# EasyEDA_ProPrj_Magnetic_Pole_Detector.net
KiCad netlist of a schematic drawn in EasyEDA Pro
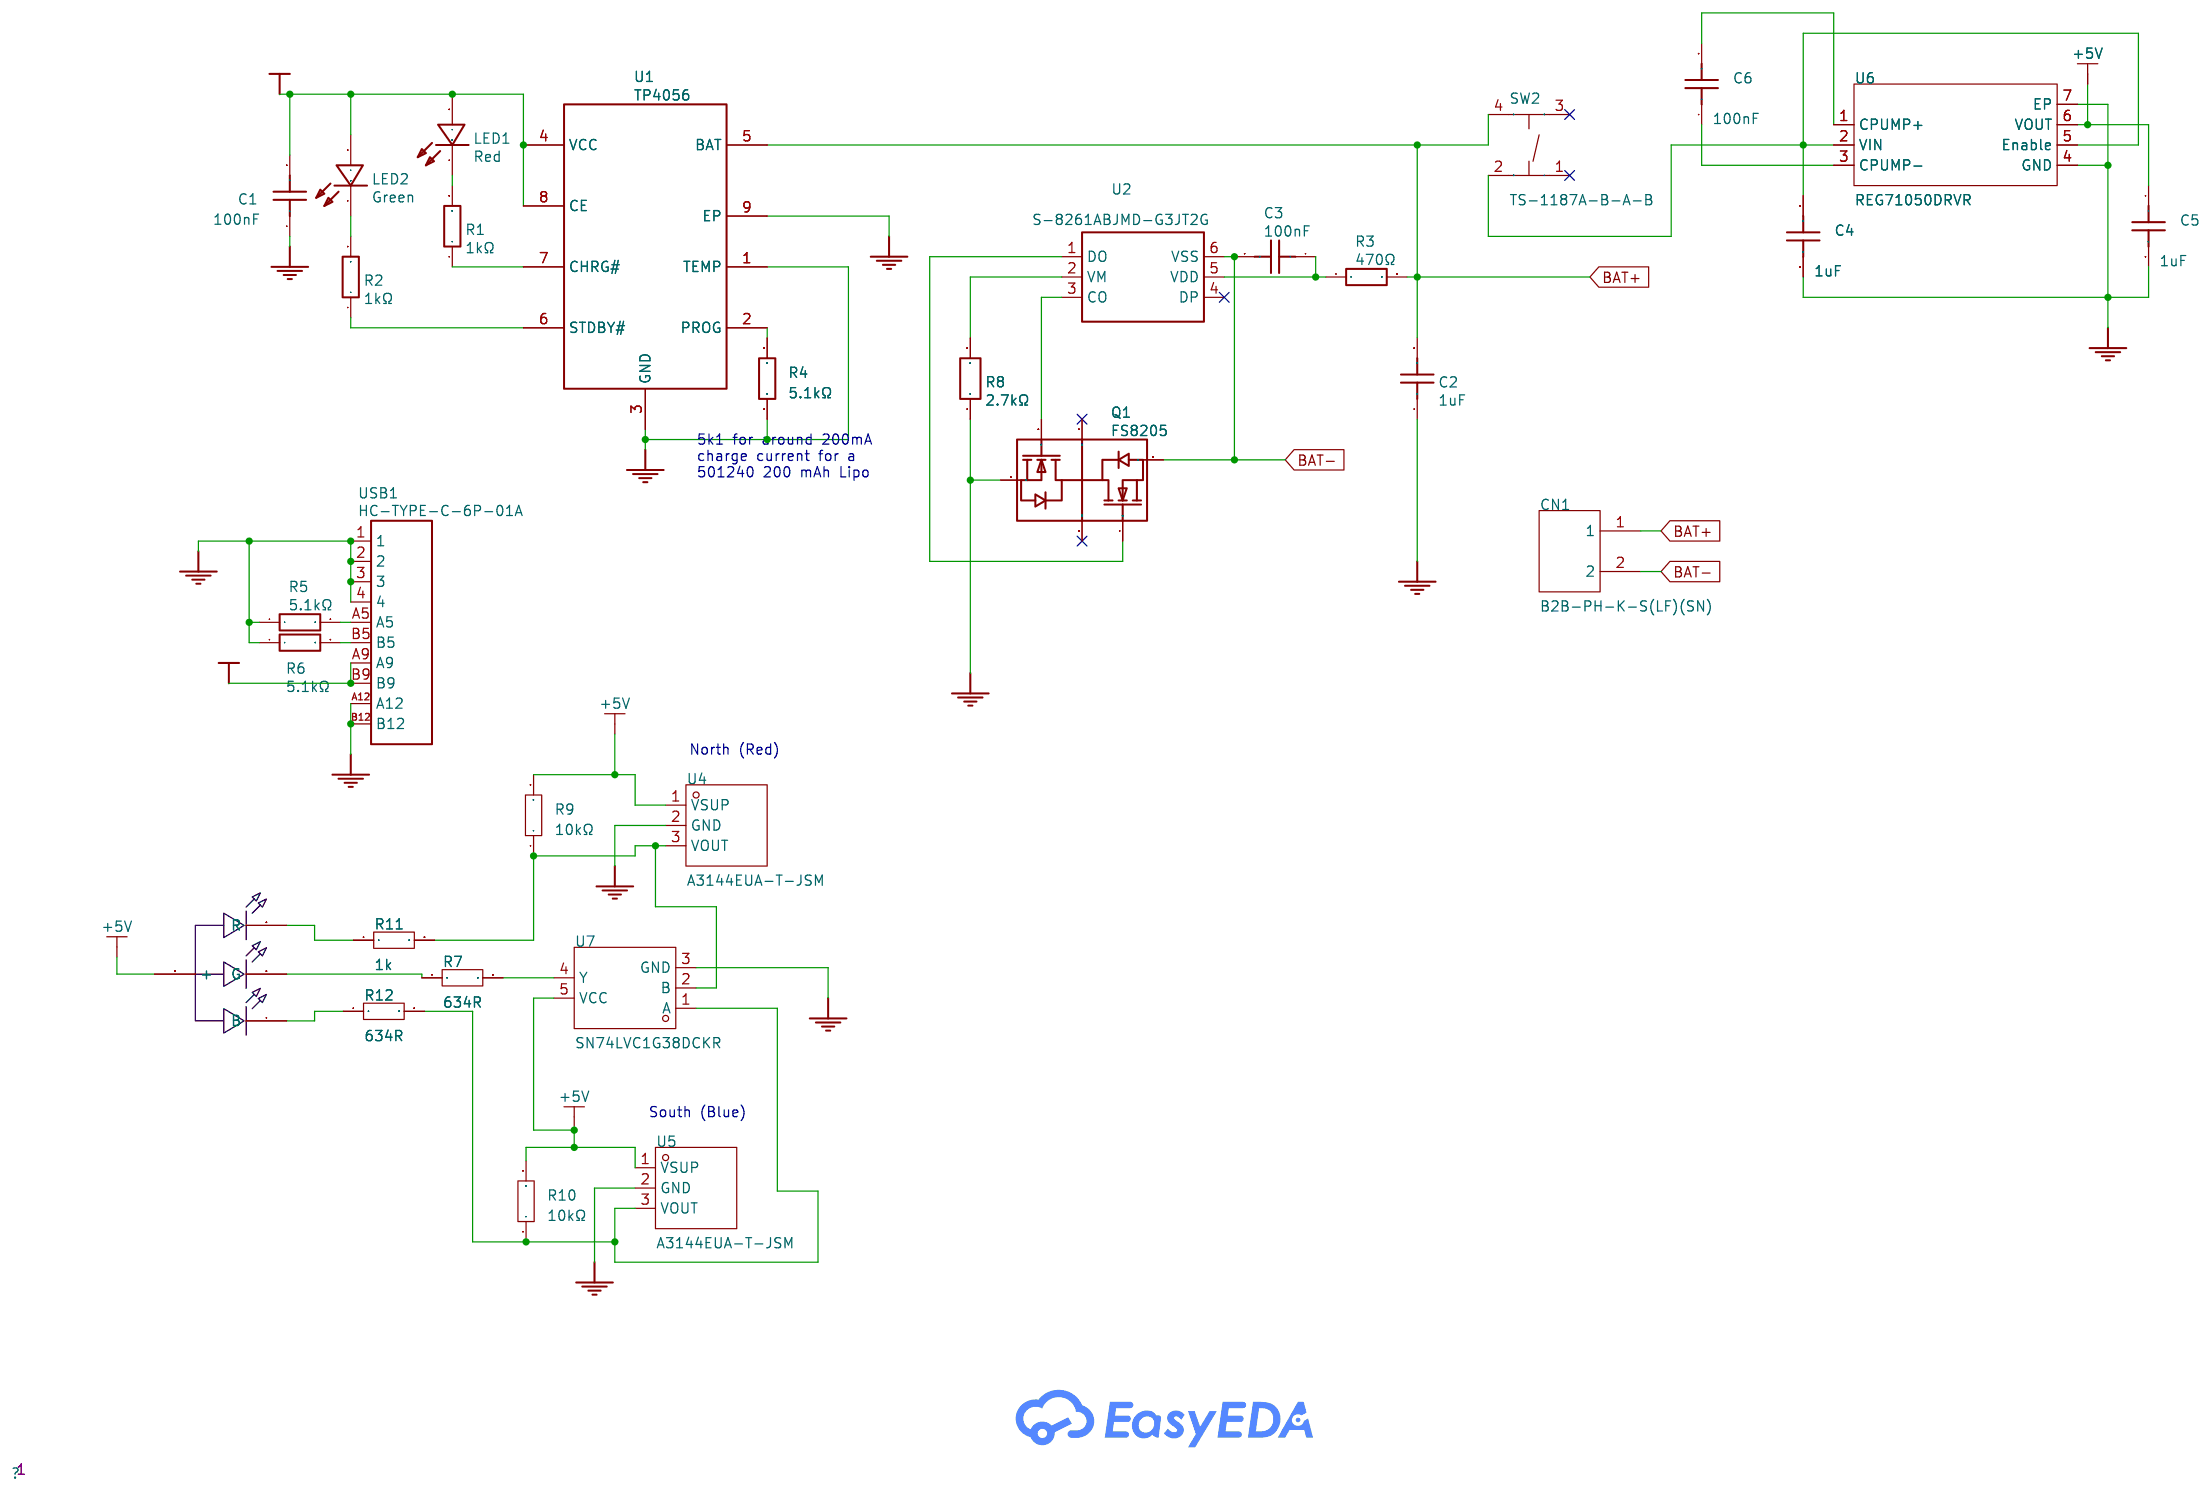
[diagram p0: schematic sheet]

(export (version "E")
  (design (tool "Eeschema 10.0.6"))
  (components
    (comp (ref "C1")
      (value "100nF")
      (footprint "easyedapro:C0402")
      (fields (field (name "Manufacturer Part") "CC0402KRX7R7BB104") (field (name "Manufacturer") "YAGEO"))
      (libsource (lib "easyedapro") (part "100nF"))
    )
    (comp (ref "C2")
      (value "1uF")
      (footprint "easyedapro:C0402")
      (fields (field (name "Manufacturer Part") "0402X106M100NT") (field (name "Manufacturer") "FH(风华)"))
      (libsource (lib "easyedapro") (part "10uF"))
    )
    (comp (ref "C3")
      (value "100nF")
      (footprint "easyedapro:C0402")
      (fields (field (name "Manufacturer Part") "CC0402KRX7R7BB104") (field (name "Manufacturer") "YAGEO"))
      (libsource (lib "easyedapro") (part "100nF"))
    )
    (comp (ref "C4")
      (value "1uF")
      (footprint "easyedapro:C0402")
      (fields (field (name "Manufacturer Part") "CC0402KRX7R7BB104") (field (name "Manufacturer") "YAGEO"))
      (libsource (lib "easyedapro") (part "100nF"))
    )
    (comp (ref "C5")
      (value "1uF")
      (footprint "easyedapro:C0402")
      (fields (field (name "Manufacturer Part") "CC0402KRX7R7BB104") (field (name "Manufacturer") "YAGEO"))
      (libsource (lib "easyedapro") (part "100nF"))
    )
    (comp (ref "C6")
      (value "100nF")
      (footprint "easyedapro:C0402")
      (fields (field (name "Manufacturer Part") "CC0402KRX7R7BB104") (field (name "Manufacturer") "YAGEO"))
      (libsource (lib "easyedapro") (part "100nF"))
    )
    (comp (ref "CN1")
      (value "B2B-PH-K-S(LF)(SN)")
      (footprint "easyedapro:CONN-TH_B2B-PH-K-S")
      (fields (field (name "Manufacturer") "JST"))
      (libsource (lib "easyedapro") (part "B2B-PH-K-S(LF)(SN)"))
    )
    (comp (ref "LED1")
      (value "Red")
      (footprint "easyedapro:LED0603-RD_RED")
      (fields
        (field (name "Manufacturer Part") "TJ-S1608SW6THBLC2R-A5")
        (field (name "Manufacturer") "TOGIALED(统佳)")
        (field (name "Contributor") "LCSC")
      )
      (libsource (lib "easyedapro") (part "Red"))
    )
    (comp (ref "LED2")
      (value "Green")
      (footprint "easyedapro:LED0603-RD_RED")
      (fields
        (field (name "Manufacturer Part") "TJ-S1608SW6TGLC7K-A5")
        (field (name "Manufacturer") "TOGIALED(统佳)")
        (field (name "Contributor") "LCSC")
      )
      (libsource (lib "easyedapro") (part "Green"))
    )
    (comp (ref "LED3")
      (value "LED 5mm RGB")
      (footprint "easyedapro:5MM RGB TRI-COLOR LED 1.25MM PINS")
      (description "Common Anode RGB LED for general purpose lighting")
      (libsource (lib "easyedapro") (part "RGB_LED_Common_Anode"))
    )
    (comp (ref "Q1")
      (value "FS8205")
      (footprint "easyedapro:SOT-23-6_L2.9-W1.6-P0.95-LS2.8-BR")
      (fields (field (name "Manufacturer Part") "FS8205A") (field (name "Manufacturer") "FUXINSEMI(富芯森美)"))
      (libsource (lib "easyedapro") (part "FS8205"))
    )
    (comp (ref "R1")
      (value "1kΩ")
      (footprint "easyedapro:R0402")
      (fields
        (field (name "Manufacturer Part") "0402WGF1001TCE")
        (field (name "Manufacturer") "UNI-ROYAL(厚声)")
      )
      (libsource (lib "easyedapro") (part "1kΩ"))
    )
    (comp (ref "R2")
      (value "1kΩ")
      (footprint "easyedapro:R0402")
      (fields
        (field (name "Manufacturer Part") "0402WGF1001TCE")
        (field (name "Manufacturer") "UNI-ROYAL(厚声)")
      )
      (libsource (lib "easyedapro") (part "1kΩ"))
    )
    (comp (ref "R3")
      (value "470Ω")
      (footprint "easyedapro:R0402")
      (fields
        (field (name "Manufacturer Part") "0402WGF4700TCE")
        (field (name "Manufacturer") "UNI-ROYAL(厚声)")
      )
      (libsource (lib "easyedapro") (part "470Ω"))
    )
    (comp (ref "R4")
      (value "5.1kΩ")
      (footprint "easyedapro:R0402")
      (fields
        (field (name "Manufacturer Part") "0402WGF5101TCE")
        (field (name "Manufacturer") "UNI-ROYAL(厚声)")
      )
      (libsource (lib "easyedapro") (part "5.1kΩ"))
    )
    (comp (ref "R5")
      (value "5.1kΩ")
      (footprint "easyedapro:R0402")
      (fields
        (field (name "Manufacturer Part") "0402WGF5101TCE")
        (field (name "Manufacturer") "UNI-ROYAL(厚声)")
      )
      (libsource (lib "easyedapro") (part "5.1kΩ"))
    )
    (comp (ref "R6")
      (value "5.1kΩ")
      (footprint "easyedapro:R0402")
      (fields
        (field (name "Manufacturer Part") "0402WGF5101TCE")
        (field (name "Manufacturer") "UNI-ROYAL(厚声)")
      )
      (libsource (lib "easyedapro") (part "5.1kΩ"))
    )
    (comp (ref "R7")
      (value "634R")
      (footprint "easyedapro:R0603")
      (libsource (lib "easyedapro") (part "Res"))
    )
    (comp (ref "R8")
      (value "2.7kΩ")
      (footprint "easyedapro:R0402")
      (fields
        (field (name "Manufacturer Part") "0402WGF2701TCE")
        (field (name "Manufacturer") "UNI-ROYAL(厚声)")
        (field (name "Contributor") "LCSC")
      )
      (libsource (lib "easyedapro") (part "2.7kΩ"))
    )
    (comp (ref "R9")
      (value "10kΩ")
      (footprint "easyedapro:R0603")
      (fields (field (name "Manufacturer Part") "FCR0402F10K") (field (name "Manufacturer") "VO(翔胜)"))
      (libsource (lib "easyedapro") (part "Res"))
    )
    (comp (ref "R10")
      (value "10kΩ")
      (footprint "easyedapro:R0603")
      (fields (field (name "Manufacturer Part") "SCR0402F10K") (field (name "Manufacturer") "VO(翔胜)"))
      (libsource (lib "easyedapro") (part "Res"))
    )
    (comp (ref "R11") (value "1k") (footprint "easyedapro:R0603") (libsource (lib "easyedapro") (part "Res")))
    (comp (ref "R12")
      (value "634R")
      (footprint "easyedapro:R0603")
      (libsource (lib "easyedapro") (part "Res"))
    )
    (comp (ref "SW2")
      (value "TS-1187A-B-A-B")
      (footprint "easyedapro:SW-SMD_4P-L5.1-W5.1-P3.70-LS6.5-TL_H1.5")
      (fields (field (name "Manufacturer") "XKB Connection(中国星坤)"))
      (libsource (lib "easyedapro") (part "TS-1187A-B-A-B"))
    )
    (comp (ref "U1")
      (value "TP4056")
      (footprint "easyedapro:ESOP-8_L4.9-W3.9-P1.27-LS6.0-BL-EP")
      (fields (field (name "Manufacturer") "UMW") (field (name "Contributor") "Guest"))
      (libsource (lib "easyedapro") (part "TP4056"))
    )
    (comp (ref "U2")
      (value "S-8261ABJMD-G3JT2G")
      (footprint "easyedapro:SOT-23-6_L2.9-W1.6-P0.95-LS2.8-TL")
      (fields
        (field (name "Manufacturer Part") "S-8261ABJMD-G3JT2S")
        (field (name "Manufacturer") "ABLIC(艾普凌科)")
      )
      (libsource (lib "easyedapro") (part "S-8261ABJMD-G3JT2G"))
    )
    (comp (ref "U4")
      (value "A3144EUA-T-JSM")
      (footprint "easyedapro:TO-92S-3_L4.1-W1.7-P1.27-L")
      (fields (field (name "Manufacturer") "JSMSEMI(杰盛微)"))
      (libsource (lib "easyedapro") (part "A3144EUA-T-JSM"))
    )
    (comp (ref "U5")
      (value "A3144EUA-T-JSM")
      (footprint "easyedapro:TO-92S-3_L4.1-W1.7-P1.27-L")
      (fields (field (name "Manufacturer") "JSMSEMI(杰盛微)"))
      (libsource (lib "easyedapro") (part "A3144EUA-T-JSM"))
    )
    (comp (ref "U6")
      (value "REG71050DRVR")
      (footprint "easyedapro:WSON-6_L2.0-W2.0-P0.65-TL-EP")
      (fields (field (name "Manufacturer") "TI(德州仪器)"))
      (libsource (lib "easyedapro") (part "REG71050DRVR"))
    )
    (comp (ref "U7")
      (value "SN74LVC1G38DCKR")
      (footprint "easyedapro:SC-70-5_L2.1-W1.3-P0.65-LS2.1-BL")
      (fields (field (name "Manufacturer") "TI(德州仪器)"))
      (libsource (lib "easyedapro") (part "SN74LVC1G38DCKR"))
    )
    (comp (ref "USB1")
      (value "HC-TYPE-C-6P-01A")
      (footprint "easyedapro:USB-C-SMD_HC-TYPE-C-6P-01A")
      (fields (field (name "Manufacturer") "HCTL(华灿天禄)") (field (name "Contributor") "LCSC"))
      (libsource (lib "easyedapro") (part "HC-TYPE-C-6P-01A"))
    )
  )
  (nets
    (net (code "1") (name "+5V") (class "Default")
      (node (ref "C5") (pin "1") (pinfunction "1_1") (pintype "unspecified"))
      (node (ref "LED3") (pin "1") (pinfunction "+_1") (pintype "input"))
      (node (ref "R10") (pin "2") (pinfunction "2_2") (pintype "input"))
      (node (ref "R9") (pin "2") (pinfunction "2_2") (pintype "input"))
      (node (ref "U4") (pin "1") (pinfunction "VSUP_1") (pintype "unspecified"))
      (node (ref "U5") (pin "1") (pinfunction "VSUP_1") (pintype "unspecified"))
      (node (ref "U6") (pin "6") (pinfunction "VOUT_6") (pintype "unspecified"))
      (node (ref "U7") (pin "5") (pinfunction "VCC_5") (pintype "unspecified"))
    )
    (net (code "2") (name "BAT+") (class "Default")
      (node (ref "C2") (pin "2") (pinfunction "2_2") (pintype "unspecified"))
      (node (ref "CN1") (pin "1") (pinfunction "1_1") (pintype "input"))
      (node (ref "R3") (pin "2") (pinfunction "2_2") (pintype "input"))
      (node (ref "SW2") (pin "4") (pinfunction "D_4") (pintype "unspecified"))
      (node (ref "U1") (pin "5") (pinfunction "BAT_5") (pintype "unspecified"))
    )
    (net (code "3") (name "BAT-") (class "Default")
      (node (ref "C3") (pin "2") (pinfunction "2_2") (pintype "unspecified"))
      (node (ref "CN1") (pin "2") (pinfunction "2_2") (pintype "input"))
      (node (ref "Q1") (pin "3") (pinfunction "S2_3") (pintype "unspecified"))
      (node (ref "U2") (pin "6") (pinfunction "VSS_6") (pintype "unspecified"))
    )
    (net (code "4") (name "GND") (class "Default")
      (node (ref "C1") (pin "1") (pinfunction "1_1") (pintype "unspecified"))
      (node (ref "C2") (pin "1") (pinfunction "1_1") (pintype "unspecified"))
      (node (ref "C4") (pin "2") (pinfunction "2_2") (pintype "unspecified"))
      (node (ref "C5") (pin "2") (pinfunction "2_2") (pintype "unspecified"))
      (node (ref "Q1") (pin "1") (pinfunction "S1_1") (pintype "unspecified"))
      (node (ref "R4") (pin "1") (pinfunction "1_1") (pintype "input"))
      (node (ref "R5") (pin "1") (pinfunction "1_1") (pintype "input"))
      (node (ref "R6") (pin "1") (pinfunction "1_1") (pintype "input"))
      (node (ref "R8") (pin "1") (pinfunction "1_1") (pintype "unspecified"))
      (node (ref "U1") (pin "1") (pinfunction "TEMP_1") (pintype "unspecified"))
      (node (ref "U1") (pin "3") (pinfunction "GND_3") (pintype "unspecified"))
      (node (ref "U1") (pin "9") (pinfunction "EP_9") (pintype "unspecified"))
      (node (ref "U4") (pin "2") (pinfunction "GND_2") (pintype "unspecified"))
      (node (ref "U5") (pin "2") (pinfunction "GND_2") (pintype "unspecified"))
      (node (ref "U6") (pin "4") (pinfunction "GND_4") (pintype "unspecified"))
      (node (ref "U6") (pin "7") (pinfunction "EP_7") (pintype "unspecified"))
      (node (ref "U7") (pin "3") (pinfunction "GND_3") (pintype "unspecified"))
      (node (ref "USB1") (pin "1") (pinfunction "1_1") (pintype "unspecified"))
      (node (ref "USB1") (pin "2") (pinfunction "2_2") (pintype "unspecified"))
      (node (ref "USB1") (pin "3") (pinfunction "3_3") (pintype "unspecified"))
      (node (ref "USB1") (pin "4") (pinfunction "4_4") (pintype "unspecified"))
      (node (ref "USB1") (pin "A12") (pinfunction "A12_A12") (pintype "unspecified"))
      (node (ref "USB1") (pin "B12") (pinfunction "B12_B12") (pintype "unspecified"))
    )
    (net (code "5") (name "Net-(LED1-C)") (class "Default")
      (node (ref "LED1") (pin "1") (pinfunction "C_1") (pintype "unspecified"))
      (node (ref "R1") (pin "2") (pinfunction "2_2") (pintype "input"))
    )
    (net (code "6") (name "Net-(LED2-C)") (class "Default")
      (node (ref "LED2") (pin "1") (pinfunction "C_1") (pintype "unspecified"))
      (node (ref "R2") (pin "2") (pinfunction "2_2") (pintype "input"))
    )
    (net (code "7") (name "Net-(LED3-B)") (class "Default")
      (node (ref "LED3") (pin "4") (pinfunction "B_4") (pintype "input"))
      (node (ref "R12") (pin "1") (pinfunction "1_1") (pintype "input"))
    )
    (net (code "8") (name "Net-(LED3-G)") (class "Default")
      (node (ref "LED3") (pin "3") (pinfunction "G_3") (pintype "input"))
      (node (ref "R7") (pin "1") (pinfunction "1_1") (pintype "input"))
    )
    (net (code "9") (name "Net-(LED3-R)") (class "Default")
      (node (ref "LED3") (pin "2") (pinfunction "R_2") (pintype "input"))
      (node (ref "R11") (pin "1") (pinfunction "1_1") (pintype "input"))
    )
    (net (code "10") (name "Net-(Q1-G1)") (class "Default")
      (node (ref "Q1") (pin "6") (pinfunction "G1_6") (pintype "unspecified"))
      (node (ref "U2") (pin "3") (pinfunction "CO_3") (pintype "unspecified"))
    )
    (net (code "11") (name "Net-(Q1-G2)") (class "Default")
      (node (ref "Q1") (pin "4") (pinfunction "G2_4") (pintype "unspecified"))
      (node (ref "U2") (pin "1") (pinfunction "DO_1") (pintype "unspecified"))
    )
    (net (code "12") (name "Net-(R5-Pad2)") (class "Default")
      (node (ref "R5") (pin "2") (pinfunction "2_2") (pintype "input"))
      (node (ref "USB1") (pin "A5") (pinfunction "A5_A5") (pintype "unspecified"))
    )
    (net (code "13") (name "Net-(R6-Pad2)") (class "Default")
      (node (ref "R6") (pin "2") (pinfunction "2_2") (pintype "input"))
      (node (ref "USB1") (pin "B5") (pinfunction "B5_B5") (pintype "unspecified"))
    )
    (net (code "14") (name "Net-(SW2-B)") (class "Default")
      (node (ref "C4") (pin "1") (pinfunction "1_1") (pintype "unspecified"))
      (node (ref "SW2") (pin "2") (pinfunction "B_2") (pintype "unspecified"))
      (node (ref "U6") (pin "2") (pinfunction "VIN_2") (pintype "unspecified"))
      (node (ref "U6") (pin "5") (pinfunction "Enable_5") (pintype "unspecified"))
    )
    (net (code "15") (name "Net-(U1-CHRG#)") (class "Default")
      (node (ref "R1") (pin "1") (pinfunction "1_1") (pintype "input"))
      (node (ref "U1") (pin "7") (pinfunction "CHRG#_7") (pintype "unspecified"))
    )
    (net (code "16") (name "Net-(U1-PROG)") (class "Default")
      (node (ref "R4") (pin "2") (pinfunction "2_2") (pintype "input"))
      (node (ref "U1") (pin "2") (pinfunction "PROG_2") (pintype "unspecified"))
    )
    (net (code "17") (name "Net-(U1-STDBY#)") (class "Default")
      (node (ref "R2") (pin "1") (pinfunction "1_1") (pintype "input"))
      (node (ref "U1") (pin "6") (pinfunction "STDBY#_6") (pintype "unspecified"))
    )
    (net (code "18") (name "Net-(U2-VDD)") (class "Default")
      (node (ref "C3") (pin "1") (pinfunction "1_1") (pintype "unspecified"))
      (node (ref "R3") (pin "1") (pinfunction "1_1") (pintype "input"))
      (node (ref "U2") (pin "5") (pinfunction "VDD_5") (pintype "unspecified"))
    )
    (net (code "19") (name "Net-(U2-VM)") (class "Default")
      (node (ref "R8") (pin "2") (pinfunction "2_2") (pintype "unspecified"))
      (node (ref "U2") (pin "2") (pinfunction "VM_2") (pintype "unspecified"))
    )
    (net (code "20") (name "Net-(U4-VOUT)") (class "Default")
      (node (ref "R11") (pin "2") (pinfunction "2_2") (pintype "input"))
      (node (ref "R9") (pin "1") (pinfunction "1_1") (pintype "input"))
      (node (ref "U4") (pin "3") (pinfunction "VOUT_3") (pintype "unspecified"))
      (node (ref "U7") (pin "2") (pinfunction "B_2") (pintype "unspecified"))
    )
    (net (code "21") (name "Net-(U5-VOUT)") (class "Default")
      (node (ref "R10") (pin "1") (pinfunction "1_1") (pintype "input"))
      (node (ref "R12") (pin "2") (pinfunction "2_2") (pintype "input"))
      (node (ref "U5") (pin "3") (pinfunction "VOUT_3") (pintype "unspecified"))
      (node (ref "U7") (pin "1") (pinfunction "A_1") (pintype "unspecified"))
    )
    (net (code "22") (name "Net-(U6-CPUMP+)") (class "Default")
      (node (ref "C6") (pin "2") (pinfunction "2_2") (pintype "unspecified"))
      (node (ref "U6") (pin "1") (pinfunction "CPUMP+_1") (pintype "unspecified"))
    )
    (net (code "23") (name "Net-(U6-CPUMP-)") (class "Default")
      (node (ref "C6") (pin "1") (pinfunction "1_1") (pintype "unspecified"))
      (node (ref "U6") (pin "3") (pinfunction "CPUMP-_3") (pintype "unspecified"))
    )
    (net (code "24") (name "Net-(U7-Y)") (class "Default")
      (node (ref "R7") (pin "2") (pinfunction "2_2") (pintype "input"))
      (node (ref "U7") (pin "4") (pinfunction "Y_4") (pintype "unspecified"))
    )
    (net (code "25") (name "VBUS") (class "Default")
      (node (ref "C1") (pin "2") (pinfunction "2_2") (pintype "unspecified"))
      (node (ref "LED1") (pin "2") (pinfunction "A_2") (pintype "unspecified"))
      (node (ref "LED2") (pin "2") (pinfunction "A_2") (pintype "unspecified"))
      (node (ref "U1") (pin "4") (pinfunction "VCC_4") (pintype "unspecified"))
      (node (ref "U1") (pin "8") (pinfunction "CE_8") (pintype "unspecified"))
      (node (ref "USB1") (pin "A9") (pinfunction "A9_A9") (pintype "unspecified"))
      (node (ref "USB1") (pin "B9") (pinfunction "B9_B9") (pintype "unspecified"))
    )
    (net (code "26") (name "unconnected-(Q1-D12-Pad2)") (class "Default")
      (node (ref "Q1") (pin "2") (pinfunction "D12_2") (pintype "unspecified+no_connect"))
    )
    (net (code "27") (name "unconnected-(Q1-D12-Pad5)") (class "Default")
      (node (ref "Q1") (pin "5") (pinfunction "D12_5") (pintype "unspecified+no_connect"))
    )
    (net (code "28") (name "unconnected-(SW2-A-Pad1)") (class "Default")
      (node (ref "SW2") (pin "1") (pinfunction "A_1") (pintype "unspecified+no_connect"))
    )
    (net (code "29") (name "unconnected-(SW2-C-Pad3)") (class "Default")
      (node (ref "SW2") (pin "3") (pinfunction "C_3") (pintype "unspecified+no_connect"))
    )
    (net (code "30") (name "unconnected-(U2-DP-Pad4)") (class "Default")
      (node (ref "U2") (pin "4") (pinfunction "DP_4") (pintype "unspecified+no_connect"))
    )
  )
)
